# 04_STM32F373VBTx.net
KiCad netlist of a schematic drawn in Altium Designer
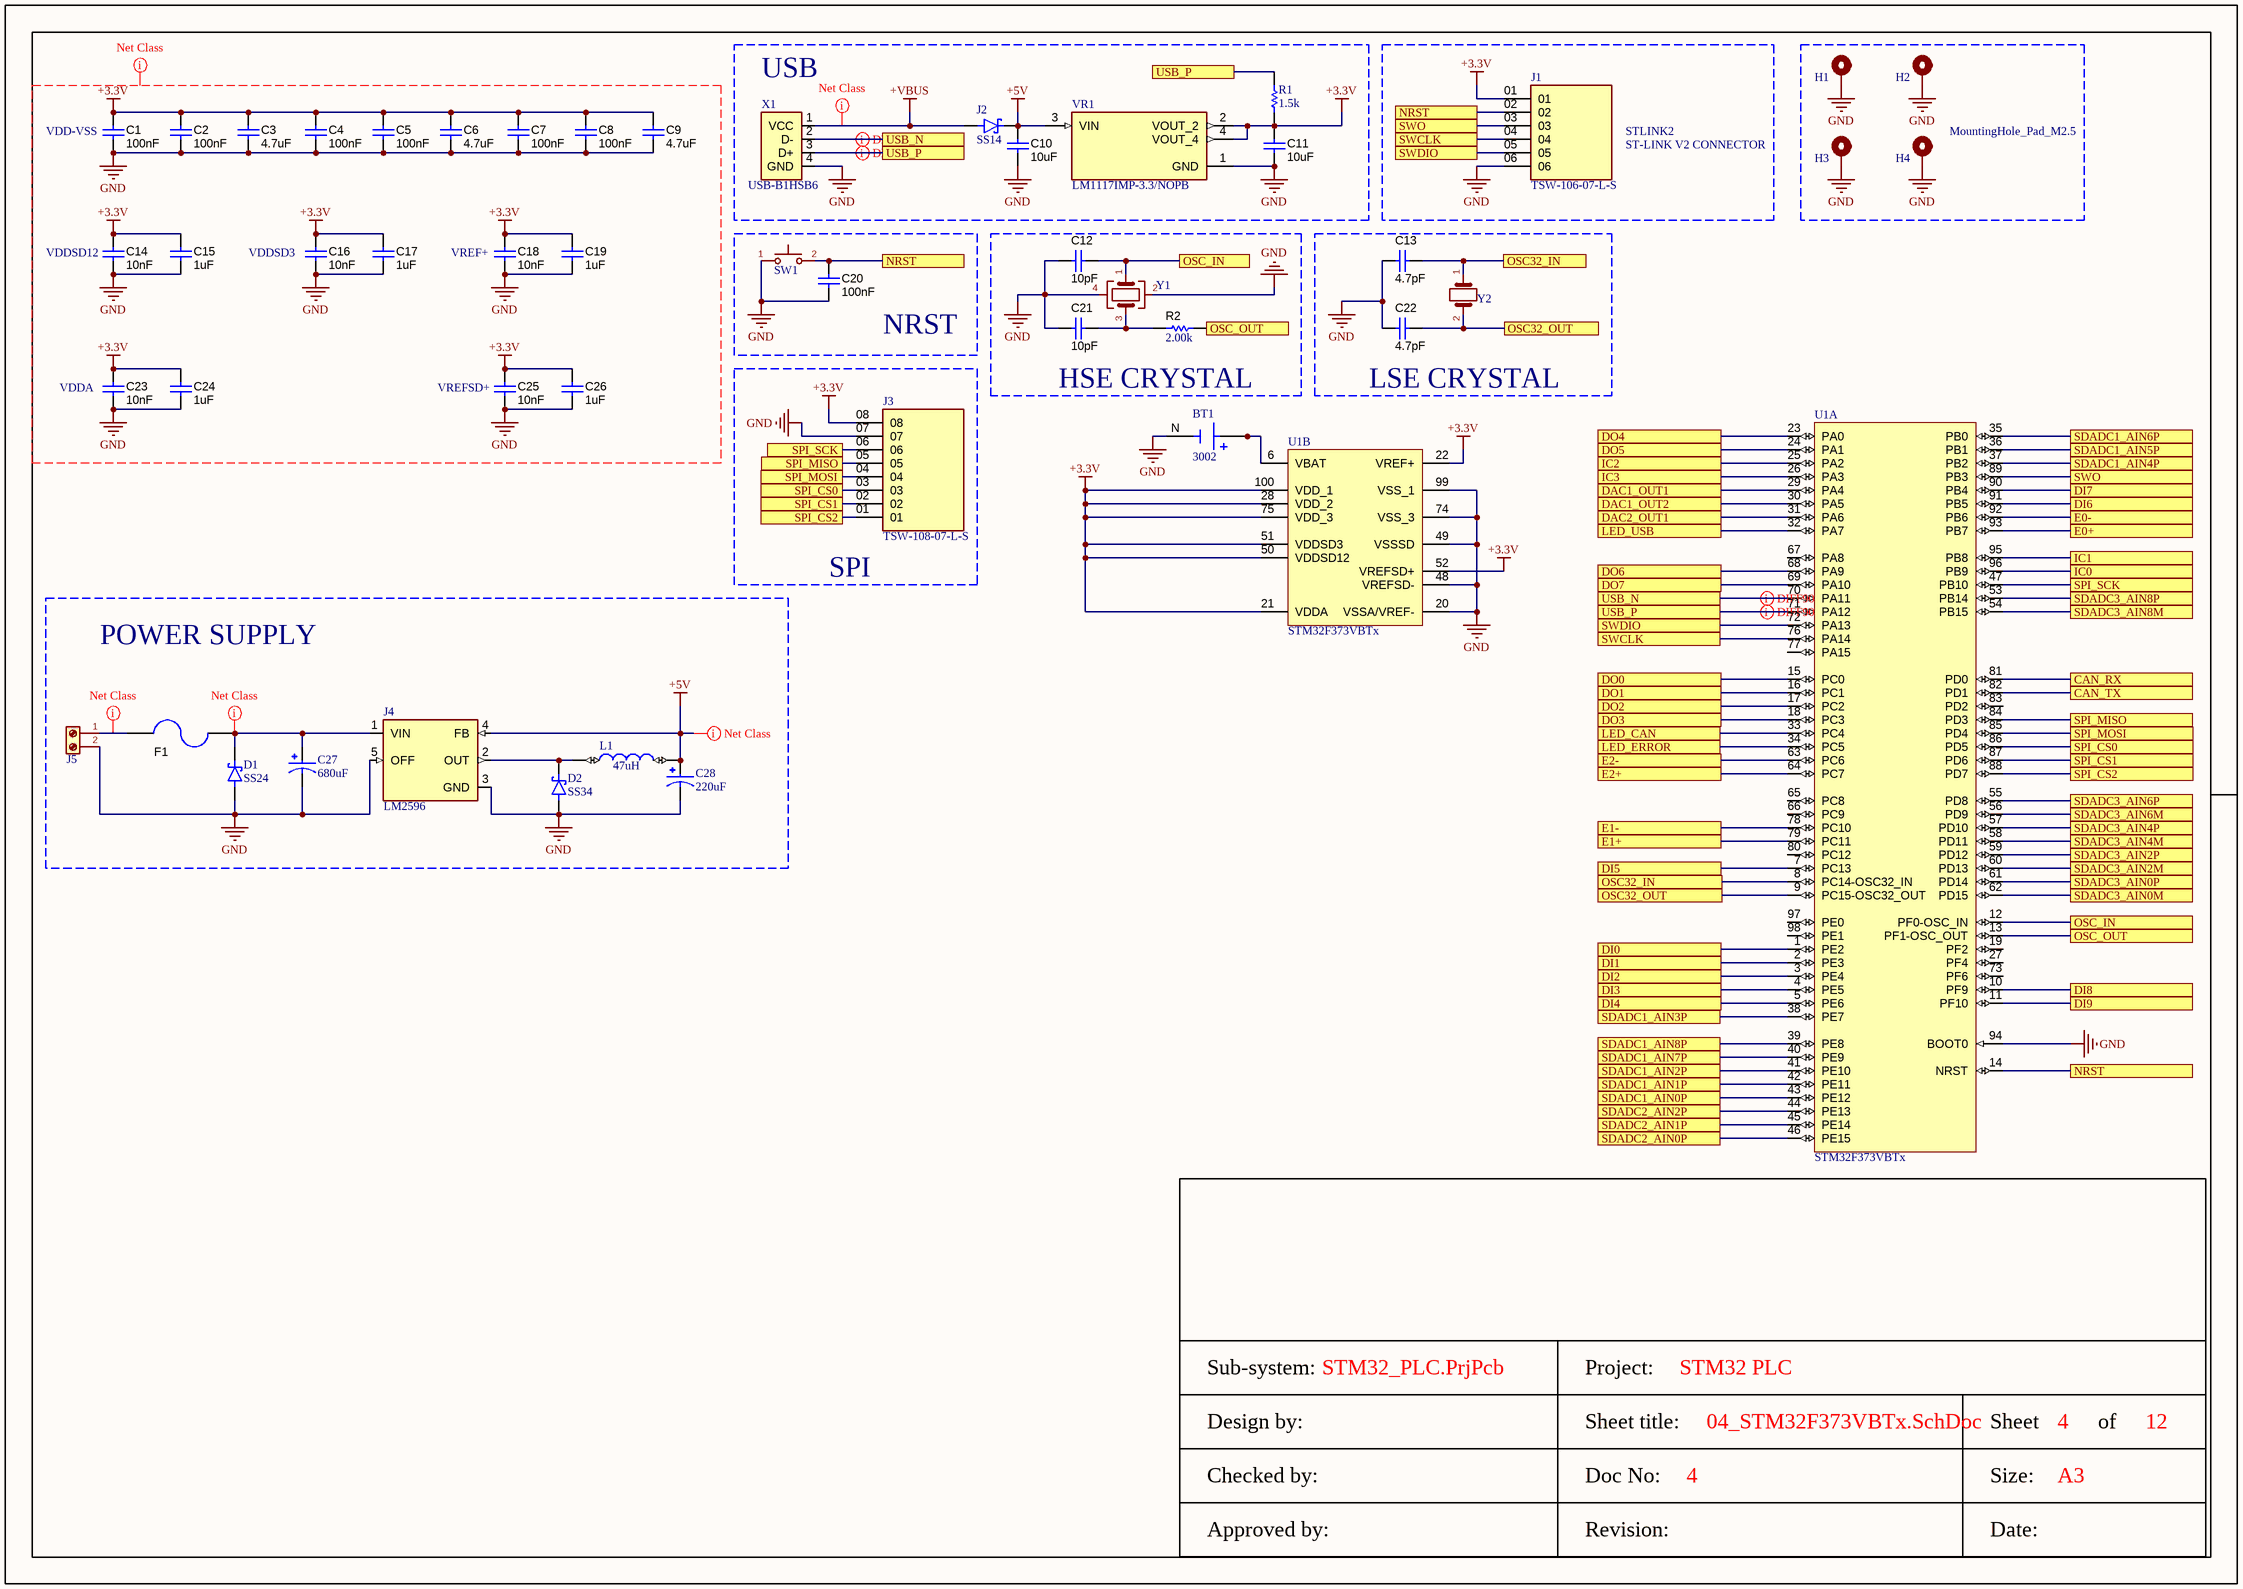
[diagram p0: 04_STM32F373VBTx.SchDoc]

(export (version "E")
  (design (tool "Eeschema 10.0.6"))
  (components
    (comp (ref "BT1")
      (value "3002")
      (footprint "BAT_3002")
      (description "Battery Holder: SMT, 1 Coin Cell, 20mm, PhosBronze/Tin-Nickel ¦ Keystone Electronics 3002")
      (fields (field (name "MF") "Keystone Electronics Corp."))
      (libsource (lib "PROC051C_AWR1843BOOST_RevC") (part "3002"))
    )
    (comp (ref "C1")
      (value "CAP 100nF 0603")
      (footprint "0603")
      (description "CAP, CERM, 100 nF, 25 V, +/- 10%, X7R, AEC-Q200 Grade 1, 0603")
      (fields
        (field (name "MANUFACTURER") "MuRata")
        (field (name "PARTNUMBER") "GCM188R70J225KE22D")
        (field (name "VALUEDISPLAYED") "100nF")
        (field (name "PUBLISHER") "Texas Instruments")
      )
      (libsource (lib "PROC051C_AWR1843BOOST_RevC") (part "CAP 100nF 0603"))
    )
    (comp (ref "C2")
      (value "CAP 100nF 0603")
      (footprint "0603")
      (description "CAP, CERM, 100 nF, 25 V, +/- 10%, X7R, AEC-Q200 Grade 1, 0603")
      (fields
        (field (name "MANUFACTURER") "MuRata")
        (field (name "PARTNUMBER") "GCM188R70J225KE22D")
        (field (name "VALUEDISPLAYED") "100nF")
        (field (name "PUBLISHER") "Texas Instruments")
      )
      (libsource (lib "PROC051C_AWR1843BOOST_RevC") (part "CAP 100nF 0603"))
    )
    (comp (ref "C3")
      (value "CAP 4.7uF 0603")
      (footprint "0603")
      (description "CAP, CERM, 4.7 uF, 10 V, +/- 10%, X7R, AEC-Q200 Grade 1, 0603")
      (fields
        (field (name "MANUFACTURER") "MuRata")
        (field (name "PARTNUMBER") "GCM188R70J225KE22D")
        (field (name "VALUEDISPLAYED") "4.7uF")
        (field (name "PUBLISHER") "Texas Instruments")
      )
      (libsource (lib "PROC051C_AWR1843BOOST_RevC") (part "CAP 4.7uF 0603"))
    )
    (comp (ref "C4")
      (value "CAP 100nF 0603")
      (footprint "0603")
      (description "CAP, CERM, 100 nF, 25 V, +/- 10%, X7R, AEC-Q200 Grade 1, 0603")
      (fields
        (field (name "MANUFACTURER") "MuRata")
        (field (name "PARTNUMBER") "GCM188R70J225KE22D")
        (field (name "VALUEDISPLAYED") "100nF")
        (field (name "PUBLISHER") "Texas Instruments")
      )
      (libsource (lib "PROC051C_AWR1843BOOST_RevC") (part "CAP 100nF 0603"))
    )
    (comp (ref "C5")
      (value "CAP 100nF 0603")
      (footprint "0603")
      (description "CAP, CERM, 100 nF, 25 V, +/- 10%, X7R, AEC-Q200 Grade 1, 0603")
      (fields
        (field (name "MANUFACTURER") "MuRata")
        (field (name "PARTNUMBER") "GCM188R70J225KE22D")
        (field (name "VALUEDISPLAYED") "100nF")
        (field (name "PUBLISHER") "Texas Instruments")
      )
      (libsource (lib "PROC051C_AWR1843BOOST_RevC") (part "CAP 100nF 0603"))
    )
    (comp (ref "C6")
      (value "CAP 4.7uF 0603")
      (footprint "0603")
      (description "CAP, CERM, 4.7 uF, 10 V, +/- 10%, X7R, AEC-Q200 Grade 1, 0603")
      (fields
        (field (name "MANUFACTURER") "MuRata")
        (field (name "PARTNUMBER") "GCM188R70J225KE22D")
        (field (name "VALUEDISPLAYED") "4.7uF")
        (field (name "PUBLISHER") "Texas Instruments")
      )
      (libsource (lib "PROC051C_AWR1843BOOST_RevC") (part "CAP 4.7uF 0603"))
    )
    (comp (ref "C7")
      (value "CAP 100nF 0603")
      (footprint "0603")
      (description "CAP, CERM, 100 nF, 25 V, +/- 10%, X7R, AEC-Q200 Grade 1, 0603")
      (fields
        (field (name "MANUFACTURER") "MuRata")
        (field (name "PARTNUMBER") "GCM188R70J225KE22D")
        (field (name "VALUEDISPLAYED") "100nF")
        (field (name "PUBLISHER") "Texas Instruments")
      )
      (libsource (lib "PROC051C_AWR1843BOOST_RevC") (part "CAP 100nF 0603"))
    )
    (comp (ref "C8")
      (value "CAP 100nF 0603")
      (footprint "0603")
      (description "CAP, CERM, 100 nF, 25 V, +/- 10%, X7R, AEC-Q200 Grade 1, 0603")
      (fields
        (field (name "MANUFACTURER") "MuRata")
        (field (name "PARTNUMBER") "GCM188R70J225KE22D")
        (field (name "VALUEDISPLAYED") "100nF")
        (field (name "PUBLISHER") "Texas Instruments")
      )
      (libsource (lib "PROC051C_AWR1843BOOST_RevC") (part "CAP 100nF 0603"))
    )
    (comp (ref "C9")
      (value "CAP 4.7uF 0603")
      (footprint "0603")
      (description "CAP, CERM, 4.7 uF, 10 V, +/- 10%, X7R, AEC-Q200 Grade 1, 0603")
      (fields
        (field (name "MANUFACTURER") "MuRata")
        (field (name "PARTNUMBER") "GCM188R70J225KE22D")
        (field (name "VALUEDISPLAYED") "4.7uF")
        (field (name "PUBLISHER") "Texas Instruments")
      )
      (libsource (lib "PROC051C_AWR1843BOOST_RevC") (part "CAP 4.7uF 0603"))
    )
    (comp (ref "C10")
      (value "GCM188R71C105KA64D")
      (footprint "0603")
      (description "CAP, CERM, 1 uF, 16 V, +/- 10%, X7R, AEC-Q200 Grade 1, 0603")
      (fields
        (field (name "MANUFACTURER") "MuRata")
        (field (name "VALUEDISPLAYED") "10uF")
        (field (name "PUBLISHER") "Texas Instruments")
      )
      (libsource (lib "PROC051C_AWR1843BOOST_RevC") (part "CAP 1uF 0603"))
    )
    (comp (ref "C11")
      (value "GCM188R71C105KA64D")
      (footprint "0603")
      (description "CAP, CERM, 1 uF, 16 V, +/- 10%, X7R, AEC-Q200 Grade 1, 0603")
      (fields
        (field (name "MANUFACTURER") "MuRata")
        (field (name "VALUEDISPLAYED") "10uF")
        (field (name "PUBLISHER") "Texas Instruments")
      )
      (libsource (lib "PROC051C_AWR1843BOOST_RevC") (part "CAP 1uF 0603"))
    )
    (comp (ref "C12")
      (value "CGA2B3X7R1H104K050BB")
      (footprint "0402L")
      (description "CAP, CERM, 10 pF, 50 V, +/- 5%, X7R, AEC-Q200 Grade 1, 0402")
      (fields
        (field (name "MANUFACTURER") "TDK")
        (field (name "VALUEDISPLAYED") "10pF")
        (field (name "PUBLISHER") "Texas Instruments")
      )
      (libsource (lib "PROC051C_AWR1843BOOST_RevC") (part "CAP 10pF 0402 50V"))
    )
    (comp (ref "C13")
      (value "GJM1555C1H4R7BB01D")
      (footprint "0402L")
      (description "CAP, CERM, 4.7 pF, 50 V, +/- 2%, C0G/NP0, 0402")
      (fields
        (field (name "MANUFACTURER") "MuRata")
        (field (name "VALUEDISPLAYED") "4.7pF")
        (field (name "PUBLISHER") "Texas Instruments")
      )
      (libsource (lib "PROC051C_AWR1843BOOST_RevC") (part "CAP 4.7pF 0402"))
    )
    (comp (ref "C14")
      (value "CAP 10nF 0603")
      (footprint "0603")
      (description "CAP, CERM, 10 nF, 50 V, +/- 10%, X7R, AEC-Q200 Grade 1, 0603")
      (fields
        (field (name "MANUFACTURER") "MuRata")
        (field (name "PARTNUMBER") "GCM188R70J225KE22D")
        (field (name "VALUEDISPLAYED") "10nF")
        (field (name "PUBLISHER") "Texas Instruments")
      )
      (libsource (lib "PROC051C_AWR1843BOOST_RevC") (part "CAP 10nF 0603"))
    )
    (comp (ref "C15")
      (value "GCM188R71C105KA64D")
      (footprint "0603")
      (description "CAP, CERM, 1 uF, 16 V, +/- 10%, X7R, AEC-Q200 Grade 1, 0603")
      (fields
        (field (name "MANUFACTURER") "MuRata")
        (field (name "VALUEDISPLAYED") "1uF")
        (field (name "PUBLISHER") "Texas Instruments")
      )
      (libsource (lib "PROC051C_AWR1843BOOST_RevC") (part "CAP 1uF 0603"))
    )
    (comp (ref "C16")
      (value "CAP 10nF 0603")
      (footprint "0603")
      (description "CAP, CERM, 10 nF, 50 V, +/- 10%, X7R, AEC-Q200 Grade 1, 0603")
      (fields
        (field (name "MANUFACTURER") "MuRata")
        (field (name "PARTNUMBER") "GCM188R70J225KE22D")
        (field (name "VALUEDISPLAYED") "10nF")
        (field (name "PUBLISHER") "Texas Instruments")
      )
      (libsource (lib "PROC051C_AWR1843BOOST_RevC") (part "CAP 10nF 0603"))
    )
    (comp (ref "C17")
      (value "GCM188R71C105KA64D")
      (footprint "0603")
      (description "CAP, CERM, 1 uF, 16 V, +/- 10%, X7R, AEC-Q200 Grade 1, 0603")
      (fields
        (field (name "MANUFACTURER") "MuRata")
        (field (name "VALUEDISPLAYED") "1uF")
        (field (name "PUBLISHER") "Texas Instruments")
      )
      (libsource (lib "PROC051C_AWR1843BOOST_RevC") (part "CAP 1uF 0603"))
    )
    (comp (ref "C18")
      (value "CAP 10nF 0603")
      (footprint "0603")
      (description "CAP, CERM, 10 nF, 50 V, +/- 10%, X7R, AEC-Q200 Grade 1, 0603")
      (fields
        (field (name "MANUFACTURER") "MuRata")
        (field (name "PARTNUMBER") "GCM188R70J225KE22D")
        (field (name "VALUEDISPLAYED") "10nF")
        (field (name "PUBLISHER") "Texas Instruments")
      )
      (libsource (lib "PROC051C_AWR1843BOOST_RevC") (part "CAP 10nF 0603"))
    )
    (comp (ref "C19")
      (value "GCM188R71C105KA64D")
      (footprint "0603")
      (description "CAP, CERM, 1 uF, 16 V, +/- 10%, X7R, AEC-Q200 Grade 1, 0603")
      (fields
        (field (name "MANUFACTURER") "MuRata")
        (field (name "VALUEDISPLAYED") "1uF")
        (field (name "PUBLISHER") "Texas Instruments")
      )
      (libsource (lib "PROC051C_AWR1843BOOST_RevC") (part "CAP 1uF 0603"))
    )
    (comp (ref "C20")
      (value "CAP 100nF 0603")
      (footprint "0603")
      (description "CAP, CERM, 100 nF, 25 V, +/- 10%, X7R, AEC-Q200 Grade 1, 0603")
      (fields
        (field (name "MANUFACTURER") "MuRata")
        (field (name "PARTNUMBER") "GCM188R70J225KE22D")
        (field (name "VALUEDISPLAYED") "100nF")
        (field (name "PUBLISHER") "Texas Instruments")
      )
      (libsource (lib "PROC051C_AWR1843BOOST_RevC") (part "CAP 100nF 0603"))
    )
    (comp (ref "C21")
      (value "CGA2B3X7R1H104K050BB")
      (footprint "0402L")
      (description "CAP, CERM, 10 pF, 50 V, +/- 5%, X7R, AEC-Q200 Grade 1, 0402")
      (fields
        (field (name "MANUFACTURER") "TDK")
        (field (name "VALUEDISPLAYED") "10pF")
        (field (name "PUBLISHER") "Texas Instruments")
      )
      (libsource (lib "PROC051C_AWR1843BOOST_RevC") (part "CAP 10pF 0402 50V"))
    )
    (comp (ref "C22")
      (value "GJM1555C1H4R7BB01D")
      (footprint "0402L")
      (description "CAP, CERM, 4.7 pF, 50 V, +/- 2%, C0G/NP0, 0402")
      (fields
        (field (name "MANUFACTURER") "MuRata")
        (field (name "VALUEDISPLAYED") "4.7pF")
        (field (name "PUBLISHER") "Texas Instruments")
      )
      (libsource (lib "PROC051C_AWR1843BOOST_RevC") (part "CAP 4.7pF 0402"))
    )
    (comp (ref "C23")
      (value "CAP 10nF 0603")
      (footprint "0603")
      (description "CAP, CERM, 10 nF, 50 V, +/- 10%, X7R, AEC-Q200 Grade 1, 0603")
      (fields
        (field (name "MANUFACTURER") "MuRata")
        (field (name "PARTNUMBER") "GCM188R70J225KE22D")
        (field (name "VALUEDISPLAYED") "10nF")
        (field (name "PUBLISHER") "Texas Instruments")
      )
      (libsource (lib "PROC051C_AWR1843BOOST_RevC") (part "CAP 10nF 0603"))
    )
    (comp (ref "C24")
      (value "GCM188R71C105KA64D")
      (footprint "0603")
      (description "CAP, CERM, 1 uF, 16 V, +/- 10%, X7R, AEC-Q200 Grade 1, 0603")
      (fields
        (field (name "MANUFACTURER") "MuRata")
        (field (name "VALUEDISPLAYED") "1uF")
        (field (name "PUBLISHER") "Texas Instruments")
      )
      (libsource (lib "PROC051C_AWR1843BOOST_RevC") (part "CAP 1uF 0603"))
    )
    (comp (ref "C25")
      (value "CAP 10nF 0603")
      (footprint "0603")
      (description "CAP, CERM, 10 nF, 50 V, +/- 10%, X7R, AEC-Q200 Grade 1, 0603")
      (fields
        (field (name "MANUFACTURER") "MuRata")
        (field (name "PARTNUMBER") "GCM188R70J225KE22D")
        (field (name "VALUEDISPLAYED") "10nF")
        (field (name "PUBLISHER") "Texas Instruments")
      )
      (libsource (lib "PROC051C_AWR1843BOOST_RevC") (part "CAP 10nF 0603"))
    )
    (comp (ref "C26")
      (value "GCM188R71C105KA64D")
      (footprint "0603")
      (description "CAP, CERM, 1 uF, 16 V, +/- 10%, X7R, AEC-Q200 Grade 1, 0603")
      (fields
        (field (name "MANUFACTURER") "MuRata")
        (field (name "VALUEDISPLAYED") "1uF")
        (field (name "PUBLISHER") "Texas Instruments")
      )
      (libsource (lib "PROC051C_AWR1843BOOST_RevC") (part "CAP 1uF 0603"))
    )
    (comp (ref "C27")
      (value "680uF")
      (footprint "CAP_EEETK1V331AQ")
      (fields (field (name "MF") "Panasonic") (field (name "MP") "EEETK1V331AQ"))
      (libsource (lib "PROC051C_AWR1843BOOST_RevC") (part "CAP ALUMINUM"))
    )
    (comp (ref "C28")
      (value "220uF")
      (footprint "CAP_EEEFT1E471AV")
      (fields (field (name "MF") "Panasonic") (field (name "MP") "EEE-FT1E471AV"))
      (libsource (lib "PROC051C_AWR1843BOOST_RevC") (part "CAP ALUMINUM 8X10.5MM"))
    )
    (comp (ref "D1")
      (value "SS24")
      (footprint "DIOM5336X265N")
      (description "Diode Schottky 40V 2A Surface Mount DO-214AA (SMB)")
      (fields (field (name "MF") "ON Semiconductor"))
      (libsource (lib "PROC051C_AWR1843BOOST_RevC") (part "SS24"))
    )
    (comp (ref "D2")
      (value "SS34")
      (footprint "DIOM5336X265N")
      (description "Diode Schottky 40V 2A Surface Mount DO-214AA (SMB)")
      (fields (field (name "MF") "ON Semiconductor") (field (name "MP") "SS24"))
      (libsource (lib "PROC051C_AWR1843BOOST_RevC") (part "SS24"))
    )
    (comp (ref "F1")
      (value "0440005.WR")
      (footprint "CAPC4520X203N")
      (description "Fuse, 5 A, 32VAC/VDC, SMD")
      (fields (field (name "MANUFACTURER") "Littelfuse"))
      (libsource (lib "PROC051C_AWR1843BOOST_RevC") (part "FUSE 1808"))
    )
    (comp (ref "H1")
      (value "MountingHole_Pad M2.5")
      (footprint "MountingHole_2.7mm_M2.5_DIN965_Pad")
      (libsource (lib "PROC051C_AWR1843BOOST_RevC") (part "MountingHole_Pad M2.5"))
    )
    (comp (ref "H2")
      (value "MountingHole_Pad M2.5")
      (footprint "MountingHole_2.7mm_M2.5_DIN965_Pad")
      (libsource (lib "PROC051C_AWR1843BOOST_RevC") (part "MountingHole_Pad M2.5"))
    )
    (comp (ref "H3")
      (value "MountingHole_Pad M2.5")
      (footprint "MountingHole_2.7mm_M2.5_DIN965_Pad")
      (libsource (lib "PROC051C_AWR1843BOOST_RevC") (part "MountingHole_Pad M2.5"))
    )
    (comp (ref "H4")
      (value "MountingHole_Pad M2.5")
      (footprint "MountingHole_2.7mm_M2.5_DIN965_Pad")
      (libsource (lib "PROC051C_AWR1843BOOST_RevC") (part "MountingHole_Pad M2.5"))
    )
    (comp (ref "J1")
      (value "TSW-106-07-L-S")
      (footprint "SAMTEC_TSW-106-07-L-S")
      (fields (field (name "MF") "Samtec Inc."))
      (libsource (lib "PROC051C_AWR1843BOOST_RevC") (part "TSW-106-07-L-S"))
    )
    (comp (ref "J2")
      (value "SS14")
      (footprint "SMA")
      (description "Diode Schottky 40 V 1A Surface Mount DO-214AC (SMA)")
      (fields (field (name "MF") "ON"))
      (libsource (lib "PROC051C_AWR1843BOOST_RevC") (part "SS14"))
    )
    (comp (ref "J3")
      (value "TSW-108-07-L-S")
      (footprint "SAMTEC_TSW-108-07-L-S")
      (fields (field (name "MF") "Samtec Inc."))
      (libsource (lib "PROC051C_AWR1843BOOST_RevC") (part "TSW-108-07-L-S"))
    )
    (comp (ref "J4")
      (value "LM2596")
      (footprint "TO263-5")
      (fields (field (name "MF") "Texas Instruments"))
      (libsource (lib "PROC051C_AWR1843BOOST_RevC") (part "LM2596"))
    )
    (comp (ref "J5")
      (value "Terminal_01x02_P5.00")
      (footprint "TerminalBlock_Phoenix_PT-1,5-2-5.0-H_1x02_P5.00mm_Horizontal")
      (libsource (lib "PROC051C_AWR1843BOOST_RevC") (part "Terminal_01x02_P5.00"))
    )
    (comp (ref "L1")
      (value "47uH")
      (footprint "INDPM120120X800N")
      (description "220 ÂµH Shielded - Inductor 1.45 A 338mOhm Max Nonstandard")
      (fields (field (name "MF") "Sumida America") (field (name "MP") "CDRH127/LDNP-221MC"))
      (libsource (lib "PROC051C_AWR1843BOOST_RevC") (part "CDRH127_LDNP-221MC"))
    )
    (comp (ref "R1")
      (value "RES 1.5K 0603")
      (footprint "0603")
      (description "RES, 1.5K, 1%, 0.1 W, AEC-Q200 Grade 0, 0603")
      (fields
        (field (name "MANUFACTURER") "Vishay-Dale")
        (field (name "PARTNUMBER") "CRCW060320R0JNEA")
        (field (name "VALUEDISPLAYED") "1.5k")
      )
      (libsource (lib "PROC051C_AWR1843BOOST_RevC") (part "RES 1.5K 0603 1%"))
    )
    (comp (ref "R2")
      (value "CRCW04021K00FKED")
      (footprint "0402L")
      (description "RES, 2.00 k, 5%, 0.063 W, AEC-Q200 Grade 0, 0402")
      (fields (field (name "MANUFACTURER") "Vishay-Dale") (field (name "VALUEDISPLAYED") "2.00k"))
      (libsource (lib "PROC051C_AWR1843BOOST_RevC") (part "RES 2K 0402"))
    )
    (comp (ref "SW1")
      (value "SW_Push 3X6x2.5MM")
      (footprint "SW_SPST_FSMSM")
      (libsource (lib "PROC051C_AWR1843BOOST_RevC") (part "SW_Push 3X6x2.5MM"))
    )
    (comp (ref "U1")
      (value "STM32F373VBTx")
      (footprint "STM-LQFP100_N")
      (fields (field (name "PARTNUMBER") "STM32F373VBT7"))
      (libsource (lib "PROC051C_AWR1843BOOST_RevC") (part "STM32F373VBT7"))
    )
    (comp (ref "VR1")
      (value "LM1117IMP-3.3/NOPB")
      (footprint "VREG_LM1117IMP-3.3/NOPB")
      (description "800-mA 15-V linear voltage regulator")
      (fields (field (name "MF") "Texas Instruments"))
      (libsource (lib "PROC051C_AWR1843BOOST_RevC") (part "LM1117IMP-3.3/NOPB"))
    )
    (comp (ref "X1")
      (value "USB-B1HSB6")
      (footprint "OST_USB-B1HSB6")
      (description "USB-B (USB TYPE-B) - Receptacle Connector 4 Position Through Hole, Right Angle")
      (fields (field (name "MF") "On Shore"))
      (libsource (lib "PROC051C_AWR1843BOOST_RevC") (part "USB-B1HSB6"))
    )
    (comp (ref "Y1")
      (value "Crystal 8MHz 3225")
      (footprint "Crystal_SMD_3225-4Pin_3.2x2.5mm_HandSoldering")
      (libsource (lib "PROC051C_AWR1843BOOST_RevC") (part "Crystal 8MHz 3225"))
    )
    (comp (ref "Y2")
      (value "Crystal 32.768KHz 3215")
      (footprint "Crystal_SMD_EuroQuartz_EQ161-2Pin_3.2x1.5mm_HandSoldering")
      (libsource (lib "PROC051C_AWR1843BOOST_RevC") (part "Crystal 32.768KHz 3215"))
    )
  )
  (nets
    (net (code "1") (name "+3.3V") (class "Default")
      (node (ref "C1") (pin "1") (pinfunction "1_1") (pintype "passive"))
      (node (ref "C11") (pin "1") (pinfunction "1_1") (pintype "passive"))
      (node (ref "C14") (pin "1") (pinfunction "1_1") (pintype "passive"))
      (node (ref "C15") (pin "1") (pinfunction "1_1") (pintype "passive"))
      (node (ref "C16") (pin "1") (pinfunction "1_1") (pintype "passive"))
      (node (ref "C17") (pin "1") (pinfunction "1_1") (pintype "passive"))
      (node (ref "C18") (pin "1") (pinfunction "1_1") (pintype "passive"))
      (node (ref "C19") (pin "1") (pinfunction "1_1") (pintype "passive"))
      (node (ref "C2") (pin "1") (pinfunction "1_1") (pintype "passive"))
      (node (ref "C23") (pin "1") (pinfunction "1_1") (pintype "passive"))
      (node (ref "C24") (pin "1") (pinfunction "1_1") (pintype "passive"))
      (node (ref "C25") (pin "1") (pinfunction "1_1") (pintype "passive"))
      (node (ref "C26") (pin "1") (pinfunction "1_1") (pintype "passive"))
      (node (ref "C3") (pin "1") (pinfunction "1_1") (pintype "passive"))
      (node (ref "C4") (pin "1") (pinfunction "1_1") (pintype "passive"))
      (node (ref "C5") (pin "1") (pinfunction "1_1") (pintype "passive"))
      (node (ref "C6") (pin "1") (pinfunction "1_1") (pintype "passive"))
      (node (ref "C7") (pin "1") (pinfunction "1_1") (pintype "passive"))
      (node (ref "C8") (pin "1") (pinfunction "1_1") (pintype "passive"))
      (node (ref "C9") (pin "1") (pinfunction "1_1") (pintype "passive"))
      (node (ref "J1") (pin "01") (pinfunction "01_01") (pintype "passive"))
      (node (ref "J3") (pin "08") (pinfunction "08_08") (pintype "passive"))
      (node (ref "R1") (pin "1") (pinfunction "1_1") (pintype "passive"))
      (node (ref "U1") (pin "100") (pinfunction "VDD_1_100") (pintype "power_in"))
      (node (ref "U1") (pin "21") (pinfunction "VDDA_21") (pintype "power_in"))
      (node (ref "U1") (pin "22") (pinfunction "VREF+_22") (pintype "power_in"))
      (node (ref "U1") (pin "28") (pinfunction "VDD_2_28") (pintype "power_in"))
      (node (ref "U1") (pin "50") (pinfunction "VDDSD12_50") (pintype "power_in"))
      (node (ref "U1") (pin "51") (pinfunction "VDDSD3_51") (pintype "power_in"))
      (node (ref "U1") (pin "52") (pinfunction "VREFSD+_52") (pintype "power_in"))
      (node (ref "U1") (pin "75") (pinfunction "VDD_3_75") (pintype "power_in"))
      (node (ref "VR1") (pin "2") (pinfunction "VOUT_2_2") (pintype "output"))
      (node (ref "VR1") (pin "4") (pinfunction "VOUT_4_4") (pintype "output"))
    )
    (net (code "2") (name "+5V") (class "Default")
      (node (ref "C10") (pin "1") (pinfunction "1_1") (pintype "passive"))
      (node (ref "C28") (pin "1") (pinfunction "1_1") (pintype "passive"))
      (node (ref "J2") (pin "P2") (pinfunction "C_P2") (pintype "passive"))
      (node (ref "J4") (pin "4") (pinfunction "FB_4") (pintype "input"))
      (node (ref "L1") (pin "2") (pinfunction "2_2") (pintype "bidirectional"))
      (node (ref "VR1") (pin "3") (pinfunction "VIN_3") (pintype "input"))
    )
    (net (code "3") (name "+VBUS") (class "Default")
      (node (ref "J2") (pin "P1") (pinfunction "A_P1") (pintype "passive"))
      (node (ref "X1") (pin "1") (pinfunction "VCC_1") (pintype "power_in"))
    )
    (net (code "4") (name "/CAN_RX") (class "Default")
      (node (ref "U1") (pin "81") (pinfunction "PD0_81") (pintype "bidirectional"))
    )
    (net (code "5") (name "/CAN_TX") (class "Default")
      (node (ref "U1") (pin "82") (pinfunction "PD1_82") (pintype "bidirectional"))
    )
    (net (code "6") (name "/DAC1_OUT1") (class "Default")
      (node (ref "U1") (pin "29") (pinfunction "PA4_29") (pintype "bidirectional"))
    )
    (net (code "7") (name "/DAC1_OUT2") (class "Default")
      (node (ref "U1") (pin "30") (pinfunction "PA5_30") (pintype "bidirectional"))
    )
    (net (code "8") (name "/DAC2_OUT1") (class "Default")
      (node (ref "U1") (pin "31") (pinfunction "PA6_31") (pintype "bidirectional"))
    )
    (net (code "9") (name "/DI0") (class "Default")
      (node (ref "U1") (pin "1") (pinfunction "PE2_1") (pintype "bidirectional"))
    )
    (net (code "10") (name "/DI1") (class "Default")
      (node (ref "U1") (pin "2") (pinfunction "PE3_2") (pintype "bidirectional"))
    )
    (net (code "11") (name "/DI2") (class "Default")
      (node (ref "U1") (pin "3") (pinfunction "PE4_3") (pintype "bidirectional"))
    )
    (net (code "12") (name "/DI3") (class "Default")
      (node (ref "U1") (pin "4") (pinfunction "PE5_4") (pintype "bidirectional"))
    )
    (net (code "13") (name "/DI4") (class "Default")
      (node (ref "U1") (pin "5") (pinfunction "PE6_5") (pintype "bidirectional"))
    )
    (net (code "14") (name "/DI5") (class "Default")
      (node (ref "U1") (pin "7") (pinfunction "PC13_7") (pintype "bidirectional"))
    )
    (net (code "15") (name "/DI6") (class "Default")
      (node (ref "U1") (pin "91") (pinfunction "PB5_91") (pintype "bidirectional"))
    )
    (net (code "16") (name "/DI7") (class "Default")
      (node (ref "U1") (pin "90") (pinfunction "PB4_90") (pintype "bidirectional"))
    )
    (net (code "17") (name "/DI8") (class "Default")
      (node (ref "U1") (pin "10") (pinfunction "PF9_10") (pintype "bidirectional"))
    )
    (net (code "18") (name "/DI9") (class "Default")
      (node (ref "U1") (pin "11") (pinfunction "PF10_11") (pintype "bidirectional"))
    )
    (net (code "19") (name "/DO0") (class "Default")
      (node (ref "U1") (pin "15") (pinfunction "PC0_15") (pintype "bidirectional"))
    )
    (net (code "20") (name "/DO1") (class "Default")
      (node (ref "U1") (pin "16") (pinfunction "PC1_16") (pintype "bidirectional"))
    )
    (net (code "21") (name "/DO2") (class "Default")
      (node (ref "U1") (pin "17") (pinfunction "PC2_17") (pintype "bidirectional"))
    )
    (net (code "22") (name "/DO3") (class "Default")
      (node (ref "U1") (pin "18") (pinfunction "PC3_18") (pintype "bidirectional"))
    )
    (net (code "23") (name "/DO4") (class "Default")
      (node (ref "U1") (pin "23") (pinfunction "PA0_23") (pintype "bidirectional"))
    )
    (net (code "24") (name "/DO5") (class "Default")
      (node (ref "U1") (pin "24") (pinfunction "PA1_24") (pintype "bidirectional"))
    )
    (net (code "25") (name "/DO6") (class "Default")
      (node (ref "U1") (pin "68") (pinfunction "PA9_68") (pintype "bidirectional"))
    )
    (net (code "26") (name "/DO7") (class "Default")
      (node (ref "U1") (pin "69") (pinfunction "PA10_69") (pintype "bidirectional"))
    )
    (net (code "27") (name "/E0+") (class "Default")
      (node (ref "U1") (pin "93") (pinfunction "PB7_93") (pintype "bidirectional"))
    )
    (net (code "28") (name "/E0-") (class "Default")
      (node (ref "U1") (pin "92") (pinfunction "PB6_92") (pintype "bidirectional"))
    )
    (net (code "29") (name "/E1+") (class "Default")
      (node (ref "U1") (pin "79") (pinfunction "PC11_79") (pintype "bidirectional"))
    )
    (net (code "30") (name "/E1-") (class "Default")
      (node (ref "U1") (pin "78") (pinfunction "PC10_78") (pintype "bidirectional"))
    )
    (net (code "31") (name "/E2+") (class "Default")
      (node (ref "U1") (pin "64") (pinfunction "PC7_64") (pintype "bidirectional"))
    )
    (net (code "32") (name "/E2-") (class "Default")
      (node (ref "U1") (pin "63") (pinfunction "PC6_63") (pintype "bidirectional"))
    )
    (net (code "33") (name "/IC0") (class "Default")
      (node (ref "U1") (pin "96") (pinfunction "PB9_96") (pintype "bidirectional"))
    )
    (net (code "34") (name "/IC1") (class "Default")
      (node (ref "U1") (pin "95") (pinfunction "PB8_95") (pintype "bidirectional"))
    )
    (net (code "35") (name "/IC2") (class "Default")
      (node (ref "U1") (pin "25") (pinfunction "PA2_25") (pintype "bidirectional"))
    )
    (net (code "36") (name "/IC3") (class "Default")
      (node (ref "U1") (pin "26") (pinfunction "PA3_26") (pintype "bidirectional"))
    )
    (net (code "37") (name "/LED_CAN") (class "Default")
      (node (ref "U1") (pin "33") (pinfunction "PC4_33") (pintype "bidirectional"))
    )
    (net (code "38") (name "/LED_ERROR") (class "Default")
      (node (ref "U1") (pin "34") (pinfunction "PC5_34") (pintype "bidirectional"))
    )
    (net (code "39") (name "/LED_USB") (class "Default")
      (node (ref "U1") (pin "32") (pinfunction "PA7_32") (pintype "bidirectional"))
    )
    (net (code "40") (name "/NRST") (class "Default")
      (node (ref "C20") (pin "1") (pinfunction "1_1") (pintype "passive"))
      (node (ref "J1") (pin "02") (pinfunction "02_02") (pintype "passive"))
      (node (ref "SW1") (pin "2") (pinfunction "2_2") (pintype "passive"))
      (node (ref "U1") (pin "14") (pinfunction "NRST_14") (pintype "bidirectional"))
    )
    (net (code "41") (name "/OSC32_IN") (class "Default")
      (node (ref "C13") (pin "1") (pinfunction "1_1") (pintype "passive"))
      (node (ref "U1") (pin "8") (pinfunction "PC14-OSC32_IN_8") (pintype "bidirectional"))
      (node (ref "Y2") (pin "1") (pinfunction "1_1") (pintype "passive"))
    )
    (net (code "42") (name "/OSC32_OUT") (class "Default")
      (node (ref "C22") (pin "1") (pinfunction "1_1") (pintype "passive"))
      (node (ref "U1") (pin "9") (pinfunction "PC15-OSC32_OUT_9") (pintype "bidirectional"))
      (node (ref "Y2") (pin "2") (pinfunction "2_2") (pintype "passive"))
    )
    (net (code "43") (name "/OSC_IN") (class "Default")
      (node (ref "C12") (pin "1") (pinfunction "1_1") (pintype "passive"))
      (node (ref "U1") (pin "12") (pinfunction "PF0-OSC_IN_12") (pintype "bidirectional"))
      (node (ref "Y1") (pin "1") (pinfunction "1_1") (pintype "passive"))
    )
    (net (code "44") (name "/OSC_OUT") (class "Default")
      (node (ref "R2") (pin "2") (pinfunction "2_2") (pintype "passive"))
      (node (ref "U1") (pin "13") (pinfunction "PF1-OSC_OUT_13") (pintype "bidirectional"))
    )
    (net (code "45") (name "/SDADC1_AIN0P") (class "Default")
      (node (ref "U1") (pin "43") (pinfunction "PE12_43") (pintype "bidirectional"))
    )
    (net (code "46") (name "/SDADC1_AIN1P") (class "Default")
      (node (ref "U1") (pin "42") (pinfunction "PE11_42") (pintype "bidirectional"))
    )
    (net (code "47") (name "/SDADC1_AIN2P") (class "Default")
      (node (ref "U1") (pin "41") (pinfunction "PE10_41") (pintype "bidirectional"))
    )
    (net (code "48") (name "/SDADC1_AIN3P") (class "Default")
      (node (ref "U1") (pin "38") (pinfunction "PE7_38") (pintype "bidirectional"))
    )
    (net (code "49") (name "/SDADC1_AIN4P") (class "Default")
      (node (ref "U1") (pin "37") (pinfunction "PB2_37") (pintype "bidirectional"))
    )
    (net (code "50") (name "/SDADC1_AIN5P") (class "Default")
      (node (ref "U1") (pin "36") (pinfunction "PB1_36") (pintype "bidirectional"))
    )
    (net (code "51") (name "/SDADC1_AIN6P") (class "Default")
      (node (ref "U1") (pin "35") (pinfunction "PB0_35") (pintype "bidirectional"))
    )
    (net (code "52") (name "/SDADC1_AIN7P") (class "Default")
      (node (ref "U1") (pin "40") (pinfunction "PE9_40") (pintype "bidirectional"))
    )
    (net (code "53") (name "/SDADC1_AIN8P") (class "Default")
      (node (ref "U1") (pin "39") (pinfunction "PE8_39") (pintype "bidirectional"))
    )
    (net (code "54") (name "/SDADC2_AIN0P") (class "Default")
      (node (ref "U1") (pin "46") (pinfunction "PE15_46") (pintype "bidirectional"))
    )
    (net (code "55") (name "/SDADC2_AIN1P") (class "Default")
      (node (ref "U1") (pin "45") (pinfunction "PE14_45") (pintype "bidirectional"))
    )
    (net (code "56") (name "/SDADC2_AIN2P") (class "Default")
      (node (ref "U1") (pin "44") (pinfunction "PE13_44") (pintype "bidirectional"))
    )
    (net (code "57") (name "/SDADC3_AIN0M") (class "Default")
      (node (ref "U1") (pin "62") (pinfunction "PD15_62") (pintype "bidirectional"))
    )
    (net (code "58") (name "/SDADC3_AIN0P") (class "Default")
      (node (ref "U1") (pin "61") (pinfunction "PD14_61") (pintype "bidirectional"))
    )
    (net (code "59") (name "/SDADC3_AIN2M") (class "Default")
      (node (ref "U1") (pin "60") (pinfunction "PD13_60") (pintype "bidirectional"))
    )
    (net (code "60") (name "/SDADC3_AIN2P") (class "Default")
      (node (ref "U1") (pin "59") (pinfunction "PD12_59") (pintype "bidirectional"))
    )
    (net (code "61") (name "/SDADC3_AIN4M") (class "Default")
      (node (ref "U1") (pin "58") (pinfunction "PD11_58") (pintype "bidirectional"))
    )
    (net (code "62") (name "/SDADC3_AIN4P") (class "Default")
      (node (ref "U1") (pin "57") (pinfunction "PD10_57") (pintype "bidirectional"))
    )
    (net (code "63") (name "/SDADC3_AIN6M") (class "Default")
      (node (ref "U1") (pin "56") (pinfunction "PD9_56") (pintype "bidirectional"))
    )
    (net (code "64") (name "/SDADC3_AIN6P") (class "Default")
      (node (ref "U1") (pin "55") (pinfunction "PD8_55") (pintype "bidirectional"))
    )
    (net (code "65") (name "/SDADC3_AIN8M") (class "Default")
      (node (ref "U1") (pin "54") (pinfunction "PB15_54") (pintype "bidirectional"))
    )
    (net (code "66") (name "/SDADC3_AIN8P") (class "Default")
      (node (ref "U1") (pin "53") (pinfunction "PB14_53") (pintype "bidirectional"))
    )
    (net (code "67") (name "/SPI_CS0") (class "Default")
      (node (ref "J3") (pin "03") (pinfunction "03_03") (pintype "passive"))
      (node (ref "U1") (pin "86") (pinfunction "PD5_86") (pintype "bidirectional"))
    )
    (net (code "68") (name "/SPI_CS1") (class "Default")
      (node (ref "J3") (pin "02") (pinfunction "02_02") (pintype "passive"))
      (node (ref "U1") (pin "87") (pinfunction "PD6_87") (pintype "bidirectional"))
    )
    (net (code "69") (name "/SPI_CS2") (class "Default")
      (node (ref "J3") (pin "01") (pinfunction "01_01") (pintype "passive"))
      (node (ref "U1") (pin "88") (pinfunction "PD7_88") (pintype "bidirectional"))
    )
    (net (code "70") (name "/SPI_MISO") (class "Default")
      (node (ref "J3") (pin "05") (pinfunction "05_05") (pintype "passive"))
      (node (ref "U1") (pin "84") (pinfunction "PD3_84") (pintype "bidirectional"))
    )
    (net (code "71") (name "/SPI_MOSI") (class "Default")
      (node (ref "J3") (pin "04") (pinfunction "04_04") (pintype "passive"))
      (node (ref "U1") (pin "85") (pinfunction "PD4_85") (pintype "bidirectional"))
    )
    (net (code "72") (name "/SPI_SCK") (class "Default")
      (node (ref "J3") (pin "06") (pinfunction "06_06") (pintype "passive"))
      (node (ref "U1") (pin "47") (pinfunction "PB10_47") (pintype "bidirectional"))
    )
    (net (code "73") (name "/SWCLK") (class "Default")
      (node (ref "J1") (pin "04") (pinfunction "04_04") (pintype "passive"))
      (node (ref "U1") (pin "76") (pinfunction "PA14_76") (pintype "bidirectional"))
    )
    (net (code "74") (name "/SWDIO") (class "Default")
      (node (ref "J1") (pin "05") (pinfunction "05_05") (pintype "passive"))
      (node (ref "U1") (pin "72") (pinfunction "PA13_72") (pintype "bidirectional"))
    )
    (net (code "75") (name "/SWO") (class "Default")
      (node (ref "J1") (pin "03") (pinfunction "03_03") (pintype "passive"))
      (node (ref "U1") (pin "89") (pinfunction "PB3_89") (pintype "bidirectional"))
    )
    (net (code "76") (name "/USB_N") (class "Default")
      (node (ref "U1") (pin "70") (pinfunction "PA11_70") (pintype "bidirectional"))
      (node (ref "X1") (pin "2") (pinfunction "D-_2") (pintype "bidirectional"))
    )
    (net (code "77") (name "/USB_P") (class "Default")
      (node (ref "R1") (pin "2") (pinfunction "2_2") (pintype "passive"))
      (node (ref "U1") (pin "71") (pinfunction "PA12_71") (pintype "bidirectional"))
      (node (ref "X1") (pin "3") (pinfunction "D+_3") (pintype "bidirectional"))
    )
    (net (code "78") (name "GND") (class "Default")
      (node (ref "BT1") (pin "N") (pinfunction "NEG_N") (pintype "passive"))
      (node (ref "C1") (pin "2") (pinfunction "2_2") (pintype "passive"))
      (node (ref "C10") (pin "2") (pinfunction "2_2") (pintype "passive"))
      (node (ref "C11") (pin "2") (pinfunction "2_2") (pintype "passive"))
      (node (ref "C12") (pin "2") (pinfunction "2_2") (pintype "passive"))
      (node (ref "C13") (pin "2") (pinfunction "2_2") (pintype "passive"))
      (node (ref "C14") (pin "2") (pinfunction "2_2") (pintype "passive"))
      (node (ref "C15") (pin "2") (pinfunction "2_2") (pintype "passive"))
      (node (ref "C16") (pin "2") (pinfunction "2_2") (pintype "passive"))
      (node (ref "C17") (pin "2") (pinfunction "2_2") (pintype "passive"))
      (node (ref "C18") (pin "2") (pinfunction "2_2") (pintype "passive"))
      (node (ref "C19") (pin "2") (pinfunction "2_2") (pintype "passive"))
      (node (ref "C2") (pin "2") (pinfunction "2_2") (pintype "passive"))
      (node (ref "C20") (pin "2") (pinfunction "2_2") (pintype "passive"))
      (node (ref "C21") (pin "2") (pinfunction "2_2") (pintype "passive"))
      (node (ref "C22") (pin "2") (pinfunction "2_2") (pintype "passive"))
      (node (ref "C23") (pin "2") (pinfunction "2_2") (pintype "passive"))
      (node (ref "C24") (pin "2") (pinfunction "2_2") (pintype "passive"))
      (node (ref "C25") (pin "2") (pinfunction "2_2") (pintype "passive"))
      (node (ref "C26") (pin "2") (pinfunction "2_2") (pintype "passive"))
      (node (ref "C27") (pin "2") (pinfunction "2_2") (pintype "passive"))
      (node (ref "C28") (pin "2") (pinfunction "2_2") (pintype "passive"))
      (node (ref "C3") (pin "2") (pinfunction "2_2") (pintype "passive"))
      (node (ref "C4") (pin "2") (pinfunction "2_2") (pintype "passive"))
      (node (ref "C5") (pin "2") (pinfunction "2_2") (pintype "passive"))
      (node (ref "C6") (pin "2") (pinfunction "2_2") (pintype "passive"))
      (node (ref "C7") (pin "2") (pinfunction "2_2") (pintype "passive"))
      (node (ref "C8") (pin "2") (pinfunction "2_2") (pintype "passive"))
      (node (ref "C9") (pin "2") (pinfunction "2_2") (pintype "passive"))
      (node (ref "D1") (pin "A") (pinfunction "A_A") (pintype "passive"))
      (node (ref "D2") (pin "A") (pinfunction "A_A") (pintype "passive"))
      (node (ref "H1") (pin "1") (pinfunction "1_1") (pintype "passive"))
      (node (ref "H2") (pin "1") (pinfunction "1_1") (pintype "passive"))
      (node (ref "H3") (pin "1") (pinfunction "1_1") (pintype "passive"))
      (node (ref "H4") (pin "1") (pinfunction "1_1") (pintype "passive"))
      (node (ref "J1") (pin "06") (pinfunction "06_06") (pintype "passive"))
      (node (ref "J3") (pin "07") (pinfunction "07_07") (pintype "passive"))
      (node (ref "J4") (pin "3") (pinfunction "GND_3") (pintype "power_in"))
      (node (ref "J4") (pin "5") (pinfunction "OFF_5") (pintype "input"))
      (node (ref "J5") (pin "2") (pinfunction "Pin_2_2") (pintype "passive"))
      (node (ref "SW1") (pin "1") (pinfunction "1_1") (pintype "passive"))
      (node (ref "U1") (pin "20") (pinfunction "VSSA/VREF-_20") (pintype "power_in"))
      (node (ref "U1") (pin "48") (pinfunction "VREFSD-_48") (pintype "power_in"))
      (node (ref "U1") (pin "49") (pinfunction "VSSSD_49") (pintype "power_in"))
      (node (ref "U1") (pin "74") (pinfunction "VSS_3_74") (pintype "power_in"))
      (node (ref "U1") (pin "94") (pinfunction "BOOT0_94") (pintype "input"))
      (node (ref "U1") (pin "99") (pinfunction "VSS_1_99") (pintype "power_in"))
      (node (ref "VR1") (pin "1") (pinfunction "GND_1") (pintype "power_in"))
      (node (ref "X1") (pin "4") (pinfunction "GND_4") (pintype "power_in"))
      (node (ref "Y1") (pin "2") (pinfunction "2_2") (pintype "passive"))
      (node (ref "Y1") (pin "4") (pinfunction "4_4") (pintype "passive"))
    )
    (net (code "79") (name "Net-(C21-Pad1)") (class "Default")
      (node (ref "C21") (pin "1") (pinfunction "1_1") (pintype "passive"))
      (node (ref "R2") (pin "1") (pinfunction "1_1") (pintype "passive"))
      (node (ref "Y1") (pin "3") (pinfunction "3_3") (pintype "passive"))
    )
    (net (code "80") (name "Net-(D1-K)") (class "Default")
      (node (ref "C27") (pin "1") (pinfunction "1_1") (pintype "passive"))
      (node (ref "D1") (pin "C") (pinfunction "K_C") (pintype "passive"))
      (node (ref "F1") (pin "1") (pinfunction "1_1") (pintype "passive"))
      (node (ref "J4") (pin "1") (pinfunction "VIN_1") (pintype "power_in"))
    )
    (net (code "81") (name "Net-(D2-K)") (class "Default")
      (node (ref "D2") (pin "C") (pinfunction "K_C") (pintype "passive"))
      (node (ref "J4") (pin "2") (pinfunction "OUT_2") (pintype "output"))
      (node (ref "L1") (pin "1") (pinfunction "1_1") (pintype "bidirectional"))
    )
    (net (code "82") (name "Net-(J5-Pin_1)") (class "Default")
      (node (ref "F1") (pin "2") (pinfunction "2_2") (pintype "passive"))
      (node (ref "J5") (pin "1") (pinfunction "Pin_1_1") (pintype "passive"))
    )
    (net (code "83") (name "Net-(U1B-VBAT)") (class "Default")
      (node (ref "BT1") (pin "P1") (pinfunction "POS_P1") (pintype "passive"))
      (node (ref "BT1") (pin "P2") (pinfunction "POS_P2") (pintype "passive"))
      (node (ref "U1") (pin "6") (pinfunction "VBAT_6") (pintype "power_in"))
    )
    (net (code "84") (name "unconnected-(U1A-PA8-Pad67)") (class "Default")
      (node (ref "U1") (pin "67") (pinfunction "PA8_67") (pintype "bidirectional"))
    )
    (net (code "85") (name "unconnected-(U1A-PA15-Pad77)") (class "Default")
      (node (ref "U1") (pin "77") (pinfunction "PA15_77") (pintype "bidirectional"))
    )
    (net (code "86") (name "unconnected-(U1A-PC8-Pad65)") (class "Default")
      (node (ref "U1") (pin "65") (pinfunction "PC8_65") (pintype "bidirectional"))
    )
    (net (code "87") (name "unconnected-(U1A-PC9-Pad66)") (class "Default")
      (node (ref "U1") (pin "66") (pinfunction "PC9_66") (pintype "bidirectional"))
    )
    (net (code "88") (name "unconnected-(U1A-PC12-Pad80)") (class "Default")
      (node (ref "U1") (pin "80") (pinfunction "PC12_80") (pintype "bidirectional"))
    )
    (net (code "89") (name "unconnected-(U1A-PD2-Pad83)") (class "Default")
      (node (ref "U1") (pin "83") (pinfunction "PD2_83") (pintype "bidirectional"))
    )
    (net (code "90") (name "unconnected-(U1A-PE0-Pad97)") (class "Default")
      (node (ref "U1") (pin "97") (pinfunction "PE0_97") (pintype "bidirectional"))
    )
    (net (code "91") (name "unconnected-(U1A-PE1-Pad98)") (class "Default")
      (node (ref "U1") (pin "98") (pinfunction "PE1_98") (pintype "bidirectional"))
    )
    (net (code "92") (name "unconnected-(U1A-PF2-Pad19)") (class "Default")
      (node (ref "U1") (pin "19") (pinfunction "PF2_19") (pintype "bidirectional"))
    )
    (net (code "93") (name "unconnected-(U1A-PF4-Pad27)") (class "Default")
      (node (ref "U1") (pin "27") (pinfunction "PF4_27") (pintype "bidirectional"))
    )
    (net (code "94") (name "unconnected-(U1A-PF6-Pad73)") (class "Default")
      (node (ref "U1") (pin "73") (pinfunction "PF6_73") (pintype "bidirectional"))
    )
  )
)
